# SCH_MulFuncPerCalendar_2024-10-28.net
KiCad netlist of a schematic drawn in EasyEDA
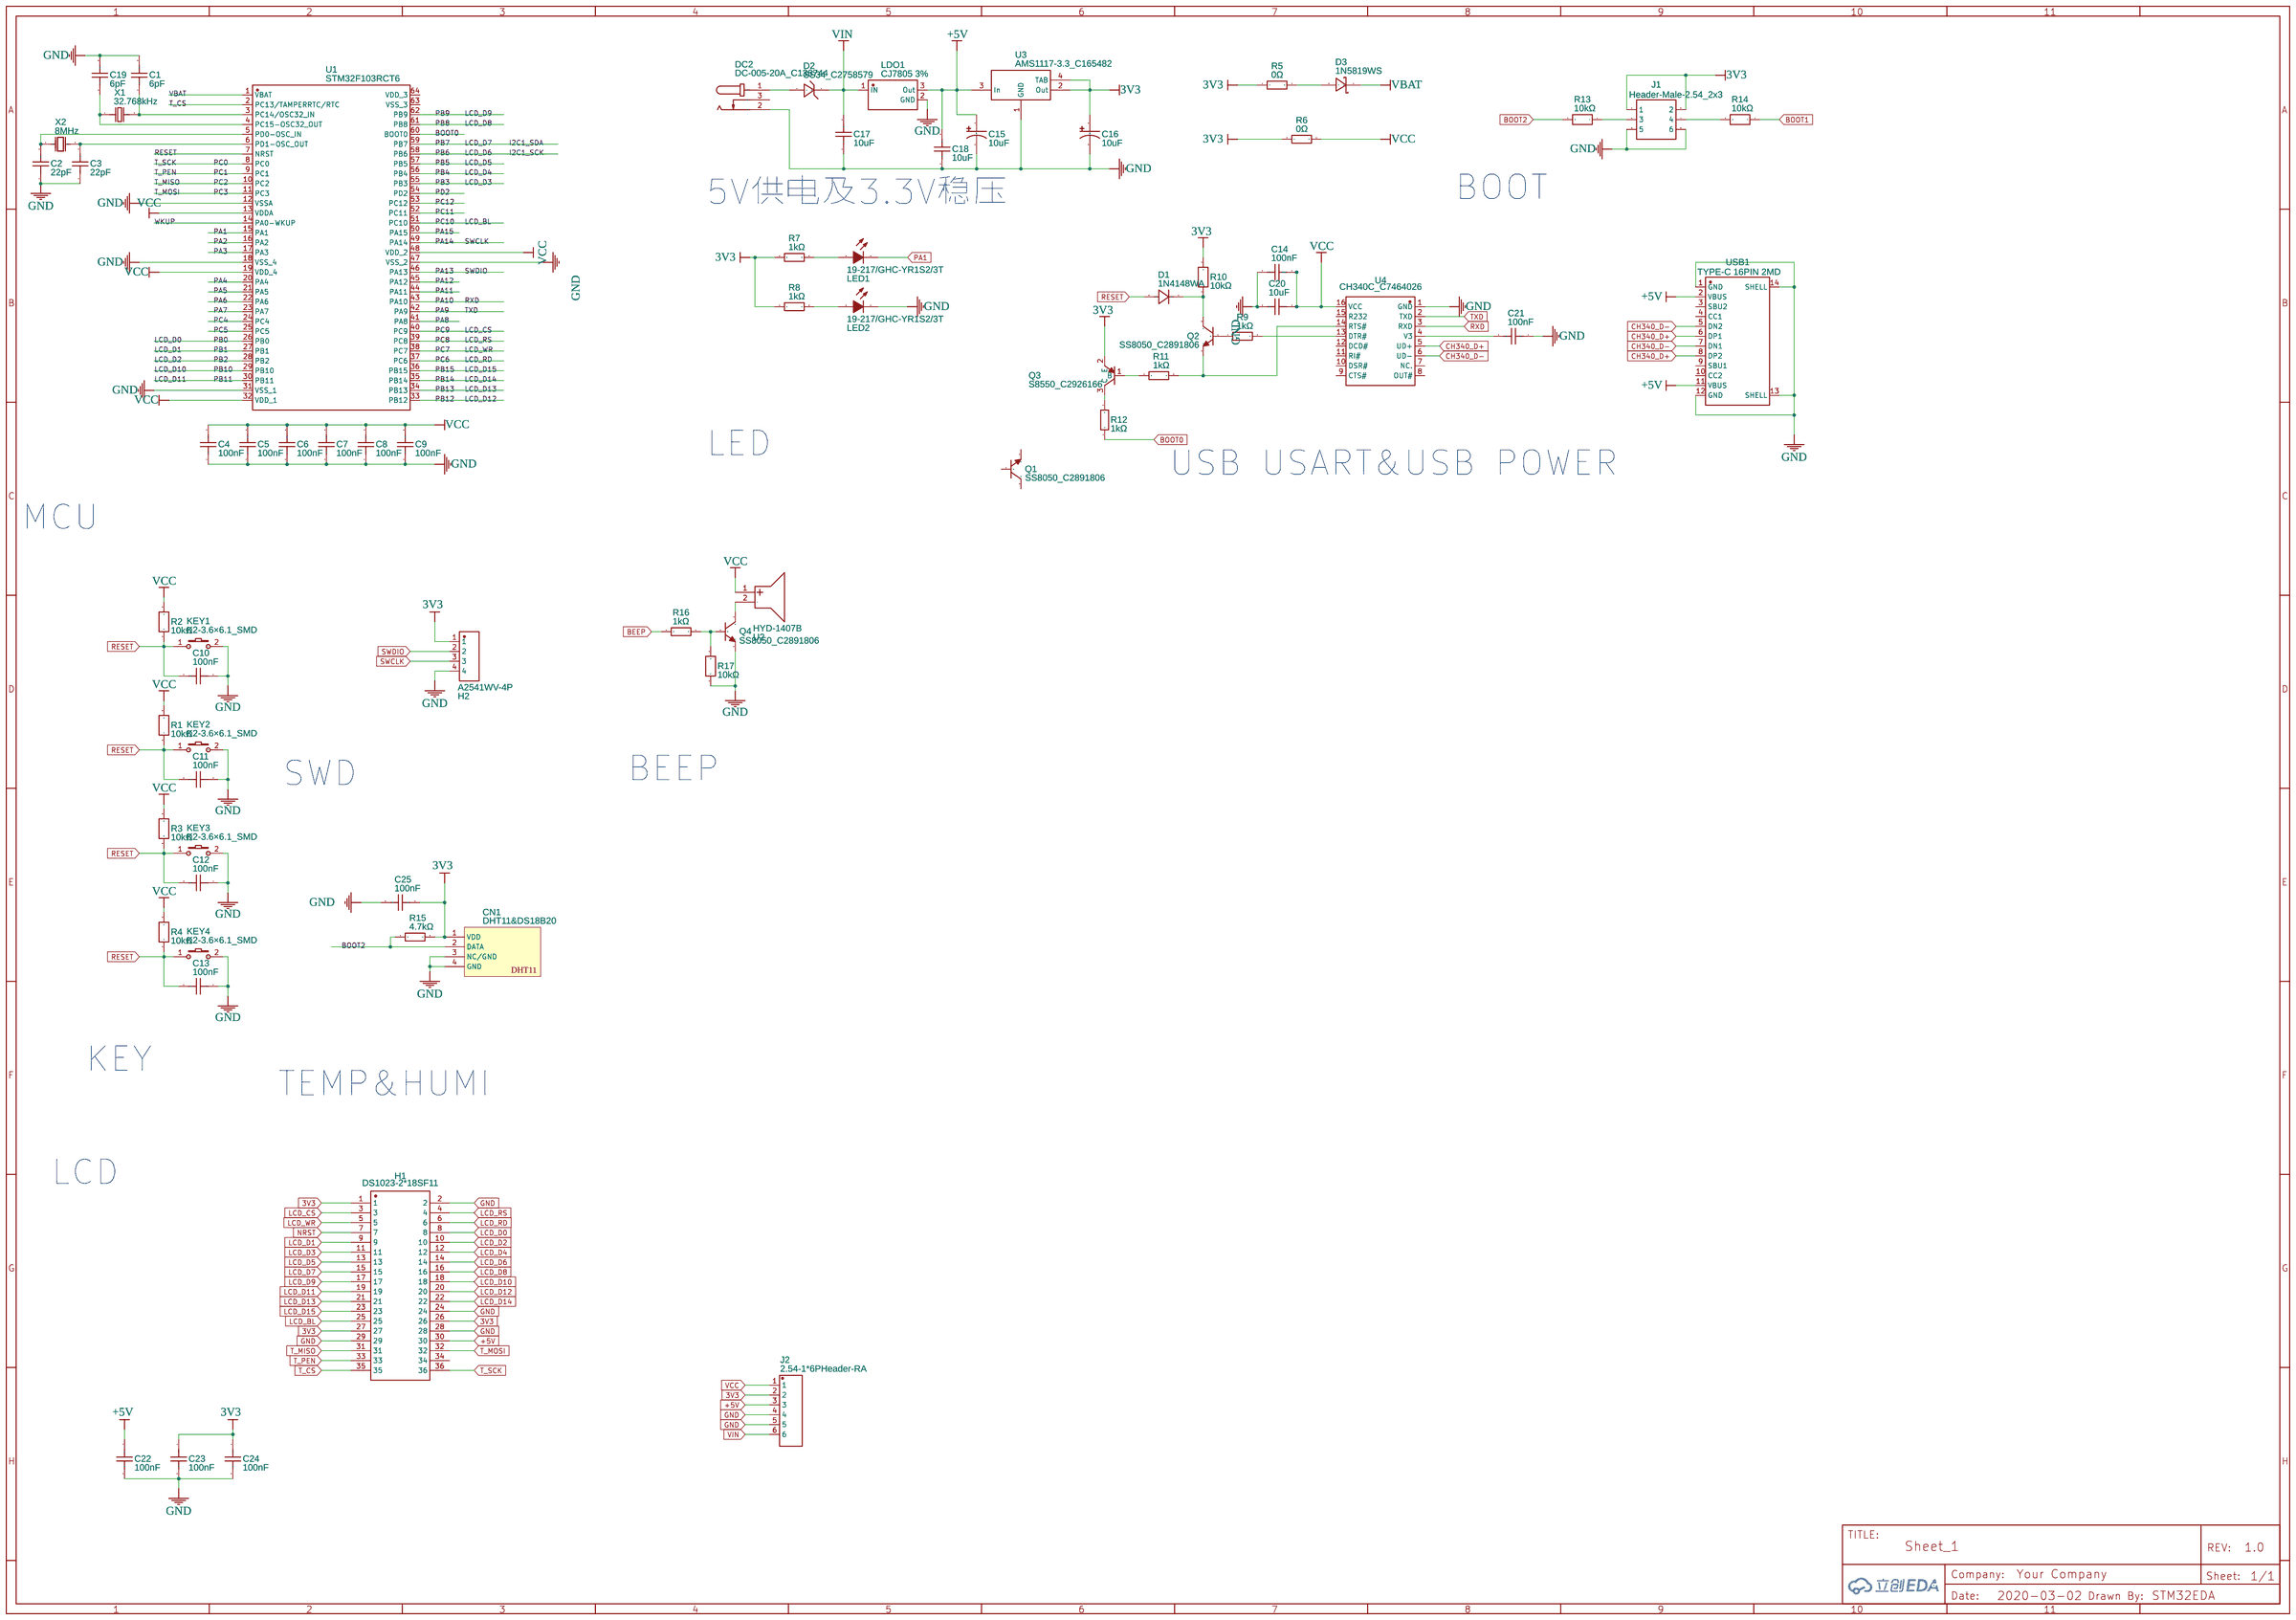
[diagram p0: schematic sheet]

(export (version "E")
  (design (tool "Eeschema 10.0.6"))
  (components
    (comp (ref "C1")
      (value "6pF")
      (fields (field (name "Manufacturer Part") "0603N6R0B500CT") (field (name "Manufacturer") "Walsin(华新科)"))
      (libsource (lib "") (part "0603N6R0B500CT"))
    )
    (comp (ref "C2")
      (value "22pF")
      (fields (field (name "Manufacturer Part") "06035A220FAT2A") (field (name "Manufacturer") "Kyocera AVX"))
      (libsource (lib "") (part "06035A220FAT2A"))
    )
    (comp (ref "C3")
      (value "22pF")
      (fields (field (name "Manufacturer Part") "06035A220FAT2A") (field (name "Manufacturer") "Kyocera AVX"))
      (libsource (lib "") (part "06035A220FAT2A"))
    )
    (comp (ref "C4")
      (value "100nF")
      (fields (field (name "Manufacturer Part") "C1608X7R1E104M080AA") (field (name "Manufacturer") "TDK"))
      (libsource (lib "") (part "C1608X7R1E104M080AA"))
    )
    (comp (ref "C5")
      (value "100nF")
      (fields (field (name "Manufacturer Part") "C1608X7R1E104M080AA") (field (name "Manufacturer") "TDK"))
      (libsource (lib "") (part "C1608X7R1E104M080AA"))
    )
    (comp (ref "C6")
      (value "100nF")
      (fields (field (name "Manufacturer Part") "C1608X7R1E104M080AA") (field (name "Manufacturer") "TDK"))
      (libsource (lib "") (part "C1608X7R1E104M080AA"))
    )
    (comp (ref "C7")
      (value "100nF")
      (fields (field (name "Manufacturer Part") "C1608X7R1E104M080AA") (field (name "Manufacturer") "TDK"))
      (libsource (lib "") (part "C1608X7R1E104M080AA"))
    )
    (comp (ref "C8")
      (value "100nF")
      (fields (field (name "Manufacturer Part") "C1608X7R1E104M080AA") (field (name "Manufacturer") "TDK"))
      (libsource (lib "") (part "C1608X7R1E104M080AA"))
    )
    (comp (ref "C9")
      (value "100nF")
      (fields (field (name "Manufacturer Part") "C1608X7R1E104M080AA") (field (name "Manufacturer") "TDK"))
      (libsource (lib "") (part "C1608X7R1E104M080AA"))
    )
    (comp (ref "C10")
      (value "100nF")
      (fields
        (field (name "Manufacturer Part") "CC0603JRX7R8BB104")
        (field (name "Manufacturer") "YAGEO(国巨)")
      )
      (libsource (lib "") (part "CC0603JRX7R8BB104"))
    )
    (comp (ref "C11")
      (value "100nF")
      (fields
        (field (name "Manufacturer Part") "CC0603JRX7R8BB104")
        (field (name "Manufacturer") "YAGEO(国巨)")
      )
      (libsource (lib "") (part "CC0603JRX7R8BB104"))
    )
    (comp (ref "C12")
      (value "100nF")
      (fields
        (field (name "Manufacturer Part") "CC0603JRX7R8BB104")
        (field (name "Manufacturer") "YAGEO(国巨)")
      )
      (libsource (lib "") (part "CC0603JRX7R8BB104"))
    )
    (comp (ref "C13")
      (value "100nF")
      (fields
        (field (name "Manufacturer Part") "CC0603JRX7R8BB104")
        (field (name "Manufacturer") "YAGEO(国巨)")
      )
      (libsource (lib "") (part "CC0603JRX7R8BB104"))
    )
    (comp (ref "C14")
      (value "100nF")
      (fields
        (field (name "Manufacturer Part") "CC0603JRX7R8BB104")
        (field (name "Manufacturer") "YAGEO(国巨)")
      )
      (libsource (lib "") (part "CC0603JRX7R8BB104"))
    )
    (comp (ref "C15")
      (value "10uF")
      (fields
        (field (name "Manufacturer Part") "CA45-A-10V-10μF-K")
        (field (name "Manufacturer") "TORCH(火炬)")
      )
      (libsource (lib "") (part "CA45-A-10V-10μF-K_1"))
    )
    (comp (ref "C16")
      (value "10uF")
      (fields
        (field (name "Manufacturer Part") "CA45-A-10V-10μF-K")
        (field (name "Manufacturer") "TORCH(火炬)")
      )
      (libsource (lib "") (part "CA45-A-10V-10μF-K"))
    )
    (comp (ref "C17")
      (value "10uF")
      (fields
        (field (name "Manufacturer Part") "GRM188R6YA106MA73D")
        (field (name "Manufacturer") "muRata(村田)")
      )
      (libsource (lib "") (part "GRM188R6YA106MA73D"))
    )
    (comp (ref "C18")
      (value "10uF")
      (fields
        (field (name "Manufacturer Part") "GRM188R6YA106MA73D")
        (field (name "Manufacturer") "muRata(村田)")
      )
      (libsource (lib "") (part "GRM188R6YA106MA73D"))
    )
    (comp (ref "C19")
      (value "6pF")
      (fields (field (name "Manufacturer Part") "0603N6R0B500CT") (field (name "Manufacturer") "Walsin(华新科)"))
      (libsource (lib "") (part "0603N6R0B500CT"))
    )
    (comp (ref "C20")
      (value "10uF")
      (fields
        (field (name "Manufacturer Part") "GRM188R6YA106MA73D")
        (field (name "Manufacturer") "muRata(村田)")
      )
      (libsource (lib "") (part "GRM188R6YA106MA73D_1"))
    )
    (comp (ref "C21")
      (value "100nF")
      (fields
        (field (name "Manufacturer Part") "CC0603JRX7R8BB104")
        (field (name "Manufacturer") "YAGEO(国巨)")
      )
      (libsource (lib "") (part "CC0603JRX7R8BB104"))
    )
    (comp (ref "C22")
      (value "100nF")
      (fields
        (field (name "Manufacturer Part") "CC0603JRX7R8BB104")
        (field (name "Manufacturer") "YAGEO(国巨)")
      )
      (libsource (lib "") (part "CC0603JRX7R8BB104_1"))
    )
    (comp (ref "C23")
      (value "100nF")
      (fields
        (field (name "Manufacturer Part") "CC0603JRX7R8BB104")
        (field (name "Manufacturer") "YAGEO(国巨)")
      )
      (libsource (lib "") (part "CC0603JRX7R8BB104_1"))
    )
    (comp (ref "C24")
      (value "100nF")
      (fields
        (field (name "Manufacturer Part") "CC0603JRX7R8BB104")
        (field (name "Manufacturer") "YAGEO(国巨)")
      )
      (libsource (lib "") (part "CC0603JRX7R8BB104_1"))
    )
    (comp (ref "C25")
      (value "100nF")
      (fields
        (field (name "Manufacturer Part") "CC0603JRX7R8BB104")
        (field (name "Manufacturer") "YAGEO(国巨)")
      )
      (libsource (lib "") (part "CC0603JRX7R8BB104"))
    )
    (comp (ref "CN1") (value "DHT11&DS18B20") (libsource (lib "") (part "DHT11&DS18B20")))
    (comp (ref "D1")
      (value "1N4148WA")
      (fields (field (name "Manufacturer") "PJSEMI(平晶微)"))
      (libsource (lib "") (part "1N4148WA"))
    )
    (comp (ref "D2")
      (value "SS34_C2758579")
      (fields (field (name "Manufacturer Part") "SS34") (field (name "Manufacturer") "UMW(友台半导体)"))
      (libsource (lib "") (part "SS34_C2758579"))
    )
    (comp (ref "D3")
      (value "1N5819WS")
      (fields (field (name "Manufacturer") "Hottech(合科泰)"))
      (libsource (lib "") (part "1N5819WS"))
    )
    (comp (ref "DC2")
      (value "DC-005-20A_C136744")
      (fields (field (name "Manufacturer Part") "DC-005-20A") (field (name "Manufacturer") "韩国韩荣"))
      (libsource (lib "") (part "DC-005-20A_C136744"))
    )
    (comp (ref "H1")
      (value "DS1023-2*18SF11")
      (fields (field (name "Manufacturer") "CONNFLY"))
      (libsource (lib "") (part "DS1023-2*18SF11"))
    )
    (comp (ref "H2")
      (value "A2541WV-4P")
      (fields (field (name "Manufacturer") "CJT(长江连接器)"))
      (libsource (lib "") (part "A2541WV-4P"))
    )
    (comp (ref "J1")
      (value "Header-Male-2.54_2x3")
      (fields (field (name "Manufacturer Part") "2.54-2*3P针") (field (name "Manufacturer") "BOOMELE(博穆精密)"))
      (libsource (lib "") (part "Header-Male-2.54_2x3"))
    )
    (comp (ref "J2")
      (value "2.54-1*6PHeader-RA")
      (fields
        (field (name "Manufacturer Part") "2.54-1*6P反弯排针")
        (field (name "Manufacturer") "BOOMELE(博穆精密)")
      )
      (libsource (lib "") (part "2.54-1*6PHeader-RA"))
    )
    (comp (ref "KEY1")
      (value "K2-3.6×6.1_SMD")
      (fields (field (name "Manufacturer Part") "K2-1107ST-A4SW-06"))
      (libsource (lib "") (part "K2-3.6×6.1_SMD"))
    )
    (comp (ref "KEY2")
      (value "K2-3.6×6.1_SMD")
      (fields (field (name "Manufacturer Part") "K2-1107ST-A4SW-06"))
      (libsource (lib "") (part "K2-3.6×6.1_SMD"))
    )
    (comp (ref "KEY3")
      (value "K2-3.6×6.1_SMD")
      (fields (field (name "Manufacturer Part") "K2-1107ST-A4SW-06"))
      (libsource (lib "") (part "K2-3.6×6.1_SMD"))
    )
    (comp (ref "KEY4")
      (value "K2-3.6×6.1_SMD")
      (fields (field (name "Manufacturer Part") "K2-1107ST-A4SW-06"))
      (libsource (lib "") (part "K2-3.6×6.1_SMD"))
    )
    (comp (ref "LDO1")
      (value "CJ7805 3%")
      (fields (field (name "Manufacturer") "CJ(江苏长电/长晶)"))
      (libsource (lib "") (part "CJ7805 3%"))
    )
    (comp (ref "LED1")
      (value "19-217/GHC-YR1S2/3T")
      (fields (field (name "Manufacturer") "EVERLIGHT(亿光)"))
      (libsource (lib "") (part "19-217/GHC-YR1S2/3T"))
    )
    (comp (ref "LED2")
      (value "19-217/GHC-YR1S2/3T")
      (fields (field (name "Manufacturer") "EVERLIGHT(亿光)"))
      (libsource (lib "") (part "19-217/GHC-YR1S2/3T"))
    )
    (comp (ref "Q1")
      (value "SS8050_C2891806")
      (fields (field (name "Manufacturer Part") "SS8050") (field (name "Manufacturer") "YONGYUTAI(永裕泰)"))
      (libsource (lib "") (part "SS8050_C2891806_2"))
    )
    (comp (ref "Q2")
      (value "SS8050_C2891806")
      (fields (field (name "Manufacturer Part") "SS8050") (field (name "Manufacturer") "YONGYUTAI(永裕泰)"))
      (libsource (lib "") (part "SS8050_C2891806"))
    )
    (comp (ref "Q3")
      (value "S8550_C2926166")
      (fields (field (name "Manufacturer Part") "S8550") (field (name "Manufacturer") "FOSAN(富信)"))
      (libsource (lib "") (part "S8550_C2926166"))
    )
    (comp (ref "Q4")
      (value "SS8050_C2891806")
      (fields (field (name "Manufacturer Part") "SS8050") (field (name "Manufacturer") "YONGYUTAI(永裕泰)"))
      (libsource (lib "") (part "SS8050_C2891806_1"))
    )
    (comp (ref "R1")
      (value "10kΩ")
      (fields
        (field (name "Manufacturer Part") "SC0603J1002F2BNRH")
        (field (name "Manufacturer") "Sunway(信维通信)")
      )
      (libsource (lib "") (part "SC0603J1002F2BNRH"))
    )
    (comp (ref "R2")
      (value "10kΩ")
      (fields
        (field (name "Manufacturer Part") "SC0603J1002F2BNRH")
        (field (name "Manufacturer") "Sunway(信维通信)")
      )
      (libsource (lib "") (part "SC0603J1002F2BNRH"))
    )
    (comp (ref "R3")
      (value "10kΩ")
      (fields
        (field (name "Manufacturer Part") "SC0603J1002F2BNRH")
        (field (name "Manufacturer") "Sunway(信维通信)")
      )
      (libsource (lib "") (part "SC0603J1002F2BNRH"))
    )
    (comp (ref "R4")
      (value "10kΩ")
      (fields
        (field (name "Manufacturer Part") "SC0603J1002F2BNRH")
        (field (name "Manufacturer") "Sunway(信维通信)")
      )
      (libsource (lib "") (part "SC0603J1002F2BNRH"))
    )
    (comp (ref "R5")
      (value "0Ω")
      (fields
        (field (name "Manufacturer Part") "0603WAF0000T5E")
        (field (name "Manufacturer") "UNI-ROYAL(厚声)")
      )
      (libsource (lib "") (part "0603WAF0000T5E"))
    )
    (comp (ref "R6")
      (value "0Ω")
      (fields
        (field (name "Manufacturer Part") "0603WAF0000T5E")
        (field (name "Manufacturer") "UNI-ROYAL(厚声)")
      )
      (libsource (lib "") (part "0603WAF0000T5E"))
    )
    (comp (ref "R7")
      (value "1kΩ")
      (fields
        (field (name "Manufacturer Part") "0603WAF1001T5E")
        (field (name "Manufacturer") "UNI-ROYAL(厚声)")
      )
      (libsource (lib "") (part "0603WAF1001T5E"))
    )
    (comp (ref "R8")
      (value "1kΩ")
      (fields
        (field (name "Manufacturer Part") "0603WAF1001T5E")
        (field (name "Manufacturer") "UNI-ROYAL(厚声)")
      )
      (libsource (lib "") (part "0603WAF1001T5E"))
    )
    (comp (ref "R9")
      (value "1kΩ")
      (fields
        (field (name "Manufacturer Part") "0603WAF1001T5E")
        (field (name "Manufacturer") "UNI-ROYAL(厚声)")
      )
      (libsource (lib "") (part "0603WAF1001T5E"))
    )
    (comp (ref "R10")
      (value "10kΩ")
      (fields
        (field (name "Manufacturer Part") "SC0603J1002F2BNRH")
        (field (name "Manufacturer") "Sunway(信维通信)")
      )
      (libsource (lib "") (part "SC0603J1002F2BNRH"))
    )
    (comp (ref "R11")
      (value "1kΩ")
      (fields
        (field (name "Manufacturer Part") "0603WAF1001T5E")
        (field (name "Manufacturer") "UNI-ROYAL(厚声)")
      )
      (libsource (lib "") (part "0603WAF1001T5E"))
    )
    (comp (ref "R12")
      (value "1kΩ")
      (fields
        (field (name "Manufacturer Part") "0603WAF1001T5E")
        (field (name "Manufacturer") "UNI-ROYAL(厚声)")
      )
      (libsource (lib "") (part "0603WAF1001T5E_2"))
    )
    (comp (ref "R13")
      (value "10kΩ")
      (fields
        (field (name "Manufacturer Part") "SC0603J1002F2BNRH")
        (field (name "Manufacturer") "Sunway(信维通信)")
      )
      (libsource (lib "") (part "SC0603J1002F2BNRH_1"))
    )
    (comp (ref "R14")
      (value "10kΩ")
      (fields
        (field (name "Manufacturer Part") "SC0603J1002F2BNRH")
        (field (name "Manufacturer") "Sunway(信维通信)")
      )
      (libsource (lib "") (part "SC0603J1002F2BNRH_1"))
    )
    (comp (ref "R15")
      (value "4.7kΩ")
      (fields (field (name "Manufacturer Part") "ACD03K4701FT") (field (name "Manufacturer") "FH(风华)"))
      (libsource (lib "") (part "4.7K  0603  SOP"))
    )
    (comp (ref "R16")
      (value "1kΩ")
      (fields
        (field (name "Manufacturer Part") "0603WAF1001T5E")
        (field (name "Manufacturer") "UNI-ROYAL(厚声)")
      )
      (libsource (lib "") (part "0603WAF1001T5E_1"))
    )
    (comp (ref "R17")
      (value "10kΩ")
      (fields
        (field (name "Manufacturer Part") "SC0603J1002F2BNRH")
        (field (name "Manufacturer") "Sunway(信维通信)")
      )
      (libsource (lib "") (part "SC0603J1002F2BNRH"))
    )
    (comp (ref "U1")
      (value "STM32F103RCT6")
      (fields (field (name "Manufacturer") "ST(意法半导体)"))
      (libsource (lib "") (part "STM32F103RCT6"))
    )
    (comp (ref "U2")
      (value "HYD-1407B")
      (fields (field (name "Manufacturer") "HYDZ(华宇)"))
      (libsource (lib "") (part "HYD-1407B"))
    )
    (comp (ref "U3")
      (value "AMS1117-3.3_C165482")
      (fields (field (name "Manufacturer Part") "SK1117-3.3") (field (name "Manufacturer") "SHIKUES(时科)"))
      (libsource (lib "") (part "AMS1117-3.3_C165482"))
    )
    (comp (ref "U4")
      (value "CH340C_C7464026")
      (fields (field (name "Manufacturer Part") "CH340C") (field (name "Manufacturer") "WCH(南京沁恒)"))
      (libsource (lib "") (part "CH340C_C7464026"))
    )
    (comp (ref "USB1")
      (value "TYPE-C 16PIN 2MD")
      (fields
        (field (name "Manufacturer Part") "TYPE-C 16PIN 2MD(073)")
        (field (name "Manufacturer") "SHOU HAN(首韩)")
      )
      (libsource (lib "") (part "TYPE-C 16PIN 2MD(073)"))
    )
    (comp (ref "X1")
      (value "32.768kHz")
      (fields (field (name "Manufacturer Part") "Q13FC13500002") (field (name "Manufacturer") "EPSON(爱普生)"))
      (libsource (lib "") (part "Q13FC1350000200"))
    )
    (comp (ref "X2")
      (value "8MHz")
      (fields
        (field (name "Manufacturer Part") "ESB8.00000F20E22")
        (field (name "Manufacturer") "HOSONIC(鸿星)")
      )
      (libsource (lib "") (part "ESB8.00000F20E22"))
    )
  )
  (nets
    (net (code "1") (name "+5V") (class "Default")
      (node (ref "C15") (pin "1") (pinfunction "1_1") (pintype "unspecified"))
      (node (ref "C18") (pin "2") (pinfunction "2_2") (pintype "unspecified"))
      (node (ref "C22") (pin "1") (pinfunction "1_1") (pintype "unspecified"))
      (node (ref "H1") (pin "30") (pinfunction "30_30") (pintype "unspecified"))
      (node (ref "J2") (pin "3") (pinfunction "3_3") (pintype "unspecified"))
      (node (ref "LDO1") (pin "3") (pinfunction "Out_3") (pintype "unspecified"))
      (node (ref "U3") (pin "3") (pinfunction "In_3") (pintype "unspecified"))
      (node (ref "USB1") (pin "11") (pinfunction "VBUS_11") (pintype "unspecified"))
      (node (ref "USB1") (pin "2") (pinfunction "VBUS_2") (pintype "unspecified"))
    )
    (net (code "2") (name "/PA2") (class "Default")
      (node (ref "U1") (pin "16") (pinfunction "PA2_16") (pintype "unspecified"))
    )
    (net (code "3") (name "/PA3") (class "Default")
      (node (ref "U1") (pin "17") (pinfunction "PA3_17") (pintype "unspecified"))
    )
    (net (code "4") (name "/PA4") (class "Default")
      (node (ref "U1") (pin "20") (pinfunction "PA4_20") (pintype "unspecified"))
    )
    (net (code "5") (name "/PA5") (class "Default")
      (node (ref "U1") (pin "21") (pinfunction "PA5_21") (pintype "unspecified"))
    )
    (net (code "6") (name "/PA6") (class "Default")
      (node (ref "U1") (pin "22") (pinfunction "PA6_22") (pintype "unspecified"))
    )
    (net (code "7") (name "/PA7") (class "Default")
      (node (ref "U1") (pin "23") (pinfunction "PA7_23") (pintype "unspecified"))
    )
    (net (code "8") (name "/PA8") (class "Default")
      (node (ref "U1") (pin "41") (pinfunction "PA8_41") (pintype "unspecified"))
    )
    (net (code "9") (name "/PA11") (class "Default")
      (node (ref "U1") (pin "44") (pinfunction "PA11_44") (pintype "unspecified"))
    )
    (net (code "10") (name "/PA12") (class "Default")
      (node (ref "U1") (pin "45") (pinfunction "PA12_45") (pintype "unspecified"))
    )
    (net (code "11") (name "/PA15") (class "Default")
      (node (ref "U1") (pin "50") (pinfunction "PA15_50") (pintype "unspecified"))
    )
    (net (code "12") (name "/PC4") (class "Default")
      (node (ref "U1") (pin "24") (pinfunction "PC4_24") (pintype "unspecified"))
    )
    (net (code "13") (name "/PC5") (class "Default")
      (node (ref "U1") (pin "25") (pinfunction "PC5_25") (pintype "unspecified"))
    )
    (net (code "14") (name "/PC11") (class "Default")
      (node (ref "U1") (pin "52") (pinfunction "PC11_52") (pintype "unspecified"))
    )
    (net (code "15") (name "/PC12") (class "Default")
      (node (ref "U1") (pin "53") (pinfunction "PC12_53") (pintype "unspecified"))
    )
    (net (code "16") (name "/PD2") (class "Default")
      (node (ref "U1") (pin "54") (pinfunction "PD2_54") (pintype "unspecified"))
    )
    (net (code "17") (name "/WKUP") (class "Default")
      (node (ref "U1") (pin "14") (pinfunction "PA0-WKUP_14") (pintype "unspecified"))
    )
    (net (code "18") (name "3V3") (class "Default")
      (node (ref "C16") (pin "1") (pinfunction "1_1") (pintype "unspecified"))
      (node (ref "C23") (pin "1") (pinfunction "1_1") (pintype "unspecified"))
      (node (ref "C24") (pin "1") (pinfunction "1_1") (pintype "unspecified"))
      (node (ref "C25") (pin "1") (pinfunction "1_1") (pintype "unspecified"))
      (node (ref "CN1") (pin "1") (pinfunction "VDD_1") (pintype "unspecified"))
      (node (ref "H1") (pin "1") (pinfunction "1_1") (pintype "unspecified"))
      (node (ref "H1") (pin "26") (pinfunction "26_26") (pintype "unspecified"))
      (node (ref "H1") (pin "27") (pinfunction "27_27") (pintype "unspecified"))
      (node (ref "H2") (pin "1") (pinfunction "1_1") (pintype "unspecified"))
      (node (ref "J1") (pin "1") (pinfunction "1_1") (pintype "input"))
      (node (ref "J1") (pin "2") (pinfunction "2_2") (pintype "input"))
      (node (ref "J2") (pin "2") (pinfunction "2_2") (pintype "unspecified"))
      (node (ref "Q3") (pin "2") (pinfunction "E_2") (pintype "input"))
      (node (ref "R10") (pin "2") (pinfunction "2_2") (pintype "unspecified"))
      (node (ref "R15") (pin "2") (pinfunction "2_2") (pintype "unspecified"))
      (node (ref "R5") (pin "1") (pinfunction "1_1") (pintype "input"))
      (node (ref "R6") (pin "1") (pinfunction "1_1") (pintype "input"))
      (node (ref "R7") (pin "1") (pinfunction "1_1") (pintype "input"))
      (node (ref "R8") (pin "1") (pinfunction "1_1") (pintype "input"))
      (node (ref "U3") (pin "2") (pinfunction "Out_2") (pintype "unspecified"))
      (node (ref "U3") (pin "4") (pinfunction "TAB_4") (pintype "unspecified"))
    )
    (net (code "19") (name "BEEP") (class "Default")
      (node (ref "R16") (pin "2") (pinfunction "2_2") (pintype "input"))
    )
    (net (code "20") (name "BOOT0") (class "Default")
      (node (ref "R12") (pin "1") (pinfunction "1_1") (pintype "input"))
      (node (ref "U1") (pin "60") (pinfunction "BOOT0_60") (pintype "unspecified"))
    )
    (net (code "21") (name "BOOT1") (class "Default")
      (node (ref "R14") (pin "1") (pinfunction "1_1") (pintype "unspecified"))
    )
    (net (code "22") (name "BOOT2") (class "Default")
      (node (ref "CN1") (pin "2") (pinfunction "DATA_2") (pintype "unspecified"))
      (node (ref "R13") (pin "2") (pinfunction "2_2") (pintype "unspecified"))
      (node (ref "R15") (pin "1") (pinfunction "1_1") (pintype "unspecified"))
    )
    (net (code "23") (name "CH340_D+") (class "Default")
      (node (ref "U4") (pin "5") (pinfunction "UD+_5") (pintype "unspecified"))
      (node (ref "USB1") (pin "6") (pinfunction "DP1_6") (pintype "unspecified"))
      (node (ref "USB1") (pin "8") (pinfunction "DP2_8") (pintype "unspecified"))
    )
    (net (code "24") (name "CH340_D-") (class "Default")
      (node (ref "U4") (pin "6") (pinfunction "UD-_6") (pintype "unspecified"))
      (node (ref "USB1") (pin "5") (pinfunction "DN2_5") (pintype "unspecified"))
      (node (ref "USB1") (pin "7") (pinfunction "DN1_7") (pintype "unspecified"))
    )
    (net (code "25") (name "GND") (class "Default")
      (node (ref "C1") (pin "2") (pinfunction "2_2") (pintype "unspecified"))
      (node (ref "C10") (pin "1") (pinfunction "1_1") (pintype "unspecified"))
      (node (ref "C11") (pin "1") (pinfunction "1_1") (pintype "unspecified"))
      (node (ref "C12") (pin "1") (pinfunction "1_1") (pintype "unspecified"))
      (node (ref "C13") (pin "1") (pinfunction "1_1") (pintype "unspecified"))
      (node (ref "C14") (pin "2") (pinfunction "2_2") (pintype "unspecified"))
      (node (ref "C15") (pin "2") (pinfunction "2_2") (pintype "unspecified"))
      (node (ref "C16") (pin "2") (pinfunction "2_2") (pintype "unspecified"))
      (node (ref "C17") (pin "1") (pinfunction "1_1") (pintype "unspecified"))
      (node (ref "C18") (pin "1") (pinfunction "1_1") (pintype "unspecified"))
      (node (ref "C19") (pin "2") (pinfunction "2_2") (pintype "unspecified"))
      (node (ref "C2") (pin "1") (pinfunction "1_1") (pintype "unspecified"))
      (node (ref "C20") (pin "2") (pinfunction "2_2") (pintype "unspecified"))
      (node (ref "C21") (pin "1") (pinfunction "1_1") (pintype "unspecified"))
      (node (ref "C22") (pin "2") (pinfunction "2_2") (pintype "unspecified"))
      (node (ref "C23") (pin "2") (pinfunction "2_2") (pintype "unspecified"))
      (node (ref "C24") (pin "2") (pinfunction "2_2") (pintype "unspecified"))
      (node (ref "C25") (pin "2") (pinfunction "2_2") (pintype "unspecified"))
      (node (ref "C3") (pin "1") (pinfunction "1_1") (pintype "unspecified"))
      (node (ref "C4") (pin "1") (pinfunction "1_1") (pintype "unspecified"))
      (node (ref "C5") (pin "1") (pinfunction "1_1") (pintype "unspecified"))
      (node (ref "C6") (pin "1") (pinfunction "1_1") (pintype "unspecified"))
      (node (ref "C7") (pin "1") (pinfunction "1_1") (pintype "unspecified"))
      (node (ref "C8") (pin "1") (pinfunction "1_1") (pintype "unspecified"))
      (node (ref "C9") (pin "1") (pinfunction "1_1") (pintype "unspecified"))
      (node (ref "CN1") (pin "3") (pinfunction "NC/GND_3") (pintype "unspecified"))
      (node (ref "CN1") (pin "4") (pinfunction "GND_4") (pintype "unspecified"))
      (node (ref "DC2") (pin "2") (pinfunction "2_2") (pintype "unspecified"))
      (node (ref "H1") (pin "2") (pinfunction "2_2") (pintype "unspecified"))
      (node (ref "H1") (pin "24") (pinfunction "24_24") (pintype "unspecified"))
      (node (ref "H1") (pin "28") (pinfunction "28_28") (pintype "unspecified"))
      (node (ref "H1") (pin "29") (pinfunction "29_29") (pintype "unspecified"))
      (node (ref "H2") (pin "4") (pinfunction "4_4") (pintype "unspecified"))
      (node (ref "J1") (pin "5") (pinfunction "5_5") (pintype "input"))
      (node (ref "J1") (pin "6") (pinfunction "6_6") (pintype "input"))
      (node (ref "J2") (pin "4") (pinfunction "4_4") (pintype "unspecified"))
      (node (ref "J2") (pin "5") (pinfunction "5_5") (pintype "unspecified"))
      (node (ref "KEY1") (pin "2") (pinfunction "2_2") (pintype "unspecified"))
      (node (ref "KEY2") (pin "2") (pinfunction "2_2") (pintype "unspecified"))
      (node (ref "KEY3") (pin "2") (pinfunction "2_2") (pintype "unspecified"))
      (node (ref "KEY4") (pin "2") (pinfunction "2_2") (pintype "unspecified"))
      (node (ref "LDO1") (pin "2") (pinfunction "GND_2") (pintype "unspecified"))
      (node (ref "LED2") (pin "1") (pinfunction "C_1") (pintype "input"))
      (node (ref "Q4") (pin "2") (pinfunction "E_2") (pintype "input"))
      (node (ref "R17") (pin "1") (pinfunction "1_1") (pintype "unspecified"))
      (node (ref "U1") (pin "12") (pinfunction "VSSA_12") (pintype "unspecified"))
      (node (ref "U1") (pin "18") (pinfunction "VSS_4_18") (pintype "unspecified"))
      (node (ref "U1") (pin "31") (pinfunction "VSS_1_31") (pintype "unspecified"))
      (node (ref "U1") (pin "47") (pinfunction "VSS_2_47") (pintype "unspecified"))
      (node (ref "U3") (pin "1") (pinfunction "GND_1") (pintype "unspecified"))
      (node (ref "U4") (pin "1") (pinfunction "GND_1") (pintype "unspecified"))
      (node (ref "USB1") (pin "1") (pinfunction "GND_1") (pintype "unspecified"))
      (node (ref "USB1") (pin "12") (pinfunction "GND_12") (pintype "unspecified"))
      (node (ref "USB1") (pin "13") (pinfunction "SHELL_13") (pintype "unspecified"))
      (node (ref "USB1") (pin "14") (pinfunction "SHELL_14") (pintype "unspecified"))
    )
    (net (code "26") (name "LCD_BL") (class "Default")
      (node (ref "H1") (pin "25") (pinfunction "25_25") (pintype "unspecified"))
      (node (ref "U1") (pin "51") (pinfunction "PC10_51") (pintype "unspecified"))
    )
    (net (code "27") (name "LCD_CS") (class "Default")
      (node (ref "H1") (pin "3") (pinfunction "3_3") (pintype "unspecified"))
      (node (ref "U1") (pin "40") (pinfunction "PC9_40") (pintype "unspecified"))
    )
    (net (code "28") (name "LCD_D0") (class "Default")
      (node (ref "H1") (pin "8") (pinfunction "8_8") (pintype "unspecified"))
      (node (ref "U1") (pin "26") (pinfunction "PB0_26") (pintype "unspecified"))
    )
    (net (code "29") (name "LCD_D1") (class "Default")
      (node (ref "H1") (pin "9") (pinfunction "9_9") (pintype "unspecified"))
      (node (ref "U1") (pin "27") (pinfunction "PB1_27") (pintype "unspecified"))
    )
    (net (code "30") (name "LCD_D2") (class "Default")
      (node (ref "H1") (pin "10") (pinfunction "10_10") (pintype "unspecified"))
      (node (ref "U1") (pin "28") (pinfunction "PB2_28") (pintype "unspecified"))
    )
    (net (code "31") (name "LCD_D3") (class "Default")
      (node (ref "H1") (pin "11") (pinfunction "11_11") (pintype "unspecified"))
      (node (ref "U1") (pin "55") (pinfunction "PB3_55") (pintype "unspecified"))
    )
    (net (code "32") (name "LCD_D4") (class "Default")
      (node (ref "H1") (pin "12") (pinfunction "12_12") (pintype "unspecified"))
      (node (ref "U1") (pin "56") (pinfunction "PB4_56") (pintype "unspecified"))
    )
    (net (code "33") (name "LCD_D5") (class "Default")
      (node (ref "H1") (pin "13") (pinfunction "13_13") (pintype "unspecified"))
      (node (ref "U1") (pin "57") (pinfunction "PB5_57") (pintype "unspecified"))
    )
    (net (code "34") (name "LCD_D6") (class "Default")
      (node (ref "H1") (pin "14") (pinfunction "14_14") (pintype "unspecified"))
      (node (ref "U1") (pin "58") (pinfunction "PB6_58") (pintype "unspecified"))
    )
    (net (code "35") (name "LCD_D7") (class "Default")
      (node (ref "H1") (pin "15") (pinfunction "15_15") (pintype "unspecified"))
      (node (ref "U1") (pin "59") (pinfunction "PB7_59") (pintype "unspecified"))
    )
    (net (code "36") (name "LCD_D8") (class "Default")
      (node (ref "H1") (pin "16") (pinfunction "16_16") (pintype "unspecified"))
      (node (ref "U1") (pin "61") (pinfunction "PB8_61") (pintype "unspecified"))
    )
    (net (code "37") (name "LCD_D9") (class "Default")
      (node (ref "H1") (pin "17") (pinfunction "17_17") (pintype "unspecified"))
      (node (ref "U1") (pin "62") (pinfunction "PB9_62") (pintype "unspecified"))
    )
    (net (code "38") (name "LCD_D10") (class "Default")
      (node (ref "H1") (pin "18") (pinfunction "18_18") (pintype "unspecified"))
      (node (ref "U1") (pin "29") (pinfunction "PB10_29") (pintype "unspecified"))
    )
    (net (code "39") (name "LCD_D11") (class "Default")
      (node (ref "H1") (pin "19") (pinfunction "19_19") (pintype "unspecified"))
      (node (ref "U1") (pin "30") (pinfunction "PB11_30") (pintype "unspecified"))
    )
    (net (code "40") (name "LCD_D12") (class "Default")
      (node (ref "H1") (pin "20") (pinfunction "20_20") (pintype "unspecified"))
      (node (ref "U1") (pin "33") (pinfunction "PB12_33") (pintype "unspecified"))
    )
    (net (code "41") (name "LCD_D13") (class "Default")
      (node (ref "H1") (pin "21") (pinfunction "21_21") (pintype "unspecified"))
      (node (ref "U1") (pin "34") (pinfunction "PB13_34") (pintype "unspecified"))
    )
    (net (code "42") (name "LCD_D14") (class "Default")
      (node (ref "H1") (pin "22") (pinfunction "22_22") (pintype "unspecified"))
      (node (ref "U1") (pin "35") (pinfunction "PB14_35") (pintype "unspecified"))
    )
    (net (code "43") (name "LCD_D15") (class "Default")
      (node (ref "H1") (pin "23") (pinfunction "23_23") (pintype "unspecified"))
      (node (ref "U1") (pin "36") (pinfunction "PB15_36") (pintype "unspecified"))
    )
    (net (code "44") (name "LCD_RD") (class "Default")
      (node (ref "H1") (pin "6") (pinfunction "6_6") (pintype "unspecified"))
      (node (ref "U1") (pin "37") (pinfunction "PC6_37") (pintype "unspecified"))
    )
    (net (code "45") (name "LCD_RS") (class "Default")
      (node (ref "H1") (pin "4") (pinfunction "4_4") (pintype "unspecified"))
      (node (ref "U1") (pin "39") (pinfunction "PC8_39") (pintype "unspecified"))
    )
    (net (code "46") (name "LCD_WR") (class "Default")
      (node (ref "H1") (pin "5") (pinfunction "5_5") (pintype "unspecified"))
      (node (ref "U1") (pin "38") (pinfunction "PC7_38") (pintype "unspecified"))
    )
    (net (code "47") (name "NRST") (class "Default")
      (node (ref "H1") (pin "7") (pinfunction "7_7") (pintype "unspecified"))
    )
    (net (code "48") (name "Net-(D1-K)") (class "Default")
      (node (ref "D1") (pin "1") (pinfunction "K_1") (pintype "unspecified"))
      (node (ref "Q2") (pin "3") (pinfunction "C_3") (pintype "input"))
      (node (ref "R10") (pin "1") (pinfunction "1_1") (pintype "unspecified"))
    )
    (net (code "49") (name "Net-(D2-A)") (class "Default")
      (node (ref "D2") (pin "2") (pinfunction "A_2") (pintype "unspecified"))
      (node (ref "DC2") (pin "1") (pinfunction "1_1") (pintype "unspecified"))
    )
    (net (code "50") (name "Net-(D3-A)") (class "Default")
      (node (ref "D3") (pin "2") (pinfunction "A_2") (pintype "unspecified"))
      (node (ref "R5") (pin "2") (pinfunction "2_2") (pintype "input"))
    )
    (net (code "51") (name "Net-(J1-Pad3)") (class "Default")
      (node (ref "J1") (pin "3") (pinfunction "3_3") (pintype "input"))
      (node (ref "R13") (pin "1") (pinfunction "1_1") (pintype "unspecified"))
    )
    (net (code "52") (name "Net-(J1-Pad4)") (class "Default")
      (node (ref "J1") (pin "4") (pinfunction "4_4") (pintype "input"))
      (node (ref "R14") (pin "2") (pinfunction "2_2") (pintype "unspecified"))
    )
    (net (code "53") (name "Net-(LED1-A)") (class "Default")
      (node (ref "LED1") (pin "2") (pinfunction "A_2") (pintype "input"))
      (node (ref "R7") (pin "2") (pinfunction "2_2") (pintype "input"))
    )
    (net (code "54") (name "Net-(LED2-A)") (class "Default")
      (node (ref "LED2") (pin "2") (pinfunction "A_2") (pintype "input"))
      (node (ref "R8") (pin "2") (pinfunction "2_2") (pintype "input"))
    )
    (net (code "55") (name "Net-(Q2-B)") (class "Default")
      (node (ref "Q2") (pin "1") (pinfunction "B_1") (pintype "input"))
      (node (ref "R9") (pin "1") (pinfunction "1_1") (pintype "input"))
    )
    (net (code "56") (name "Net-(Q2-E)") (class "Default")
      (node (ref "Q2") (pin "2") (pinfunction "E_2") (pintype "input"))
      (node (ref "R11") (pin "2") (pinfunction "2_2") (pintype "input"))
      (node (ref "U4") (pin "14") (pinfunction "RTS#_14") (pintype "unspecified"))
    )
    (net (code "57") (name "Net-(Q3-B)") (class "Default")
      (node (ref "Q3") (pin "1") (pinfunction "B_1") (pintype "input"))
      (node (ref "R11") (pin "1") (pinfunction "1_1") (pintype "input"))
    )
    (net (code "58") (name "Net-(Q3-C)") (class "Default")
      (node (ref "Q3") (pin "3") (pinfunction "C_3") (pintype "input"))
      (node (ref "R12") (pin "2") (pinfunction "2_2") (pintype "input"))
    )
    (net (code "59") (name "Net-(Q4-B)") (class "Default")
      (node (ref "Q4") (pin "1") (pinfunction "B_1") (pintype "input"))
      (node (ref "R16") (pin "1") (pinfunction "1_1") (pintype "input"))
      (node (ref "R17") (pin "2") (pinfunction "2_2") (pintype "unspecified"))
    )
    (net (code "60") (name "Net-(Q4-C)") (class "Default")
      (node (ref "Q4") (pin "3") (pinfunction "C_3") (pintype "input"))
      (node (ref "U2") (pin "2") (pinfunction "-_2") (pintype "unspecified"))
    )
    (net (code "61") (name "Net-(U1-PC14{slash}OSC32_IN)") (class "Default")
      (node (ref "C1") (pin "1") (pinfunction "1_1") (pintype "unspecified"))
      (node (ref "U1") (pin "3") (pinfunction "PC14/OSC32_IN_3") (pintype "unspecified"))
      (node (ref "X1") (pin "2") (pinfunction "2_2") (pintype "unspecified"))
    )
    (net (code "62") (name "Net-(U1-PC15-OSC32_OUT)") (class "Default")
      (node (ref "C19") (pin "1") (pinfunction "1_1") (pintype "unspecified"))
      (node (ref "U1") (pin "4") (pinfunction "PC15-OSC32_OUT_4") (pintype "unspecified"))
      (node (ref "X1") (pin "1") (pinfunction "1_1") (pintype "unspecified"))
    )
    (net (code "63") (name "Net-(U1-PD0-OSC_IN)") (class "Default")
      (node (ref "C2") (pin "2") (pinfunction "2_2") (pintype "unspecified"))
      (node (ref "U1") (pin "5") (pinfunction "PD0-OSC_IN_5") (pintype "unspecified"))
      (node (ref "X2") (pin "1") (pinfunction "OSC1_1") (pintype "input"))
    )
    (net (code "64") (name "Net-(U1-PD1-OSC_OUT)") (class "Default")
      (node (ref "C3") (pin "2") (pinfunction "2_2") (pintype "unspecified"))
      (node (ref "U1") (pin "6") (pinfunction "PD1-OSC_OUT_6") (pintype "unspecified"))
      (node (ref "X2") (pin "2") (pinfunction "OSC2_2") (pintype "input"))
    )
    (net (code "65") (name "Net-(U4-DTR#)") (class "Default")
      (node (ref "R9") (pin "2") (pinfunction "2_2") (pintype "input"))
      (node (ref "U4") (pin "13") (pinfunction "DTR#_13") (pintype "unspecified"))
    )
    (net (code "66") (name "Net-(U4-V3)") (class "Default")
      (node (ref "C21") (pin "2") (pinfunction "2_2") (pintype "unspecified"))
      (node (ref "U4") (pin "4") (pinfunction "V3_4") (pintype "unspecified"))
    )
    (net (code "67") (name "PA1") (class "Default")
      (node (ref "LED1") (pin "1") (pinfunction "C_1") (pintype "input"))
      (node (ref "U1") (pin "15") (pinfunction "PA1_15") (pintype "unspecified"))
    )
    (net (code "68") (name "RESET") (class "Default")
      (node (ref "C10") (pin "2") (pinfunction "2_2") (pintype "unspecified"))
      (node (ref "C11") (pin "2") (pinfunction "2_2") (pintype "unspecified"))
      (node (ref "C12") (pin "2") (pinfunction "2_2") (pintype "unspecified"))
      (node (ref "C13") (pin "2") (pinfunction "2_2") (pintype "unspecified"))
      (node (ref "D1") (pin "2") (pinfunction "A_2") (pintype "unspecified"))
      (node (ref "KEY1") (pin "1") (pinfunction "1_1") (pintype "unspecified"))
      (node (ref "KEY2") (pin "1") (pinfunction "1_1") (pintype "unspecified"))
      (node (ref "KEY3") (pin "1") (pinfunction "1_1") (pintype "unspecified"))
      (node (ref "KEY4") (pin "1") (pinfunction "1_1") (pintype "unspecified"))
      (node (ref "R1") (pin "1") (pinfunction "1_1") (pintype "unspecified"))
      (node (ref "R2") (pin "1") (pinfunction "1_1") (pintype "unspecified"))
      (node (ref "R3") (pin "1") (pinfunction "1_1") (pintype "unspecified"))
      (node (ref "R4") (pin "1") (pinfunction "1_1") (pintype "unspecified"))
      (node (ref "U1") (pin "7") (pinfunction "NRST_7") (pintype "unspecified"))
    )
    (net (code "69") (name "RXD") (class "Default")
      (node (ref "U1") (pin "43") (pinfunction "PA10_43") (pintype "unspecified"))
      (node (ref "U4") (pin "3") (pinfunction "RXD_3") (pintype "unspecified"))
    )
    (net (code "70") (name "SWCLK") (class "Default")
      (node (ref "H2") (pin "3") (pinfunction "3_3") (pintype "unspecified"))
      (node (ref "U1") (pin "49") (pinfunction "PA14_49") (pintype "unspecified"))
    )
    (net (code "71") (name "SWDIO") (class "Default")
      (node (ref "H2") (pin "2") (pinfunction "2_2") (pintype "unspecified"))
      (node (ref "U1") (pin "46") (pinfunction "PA13_46") (pintype "unspecified"))
    )
    (net (code "72") (name "TXD") (class "Default")
      (node (ref "U1") (pin "42") (pinfunction "PA9_42") (pintype "unspecified"))
      (node (ref "U4") (pin "2") (pinfunction "TXD_2") (pintype "unspecified"))
    )
    (net (code "73") (name "T_CS") (class "Default")
      (node (ref "H1") (pin "35") (pinfunction "35_35") (pintype "unspecified"))
      (node (ref "U1") (pin "2") (pinfunction "PC13/TAMPERRTC/RTC_2") (pintype "unspecified"))
    )
    (net (code "74") (name "T_MISO") (class "Default")
      (node (ref "H1") (pin "31") (pinfunction "31_31") (pintype "unspecified"))
      (node (ref "U1") (pin "10") (pinfunction "PC2_10") (pintype "unspecified"))
    )
    (net (code "75") (name "T_MOSI") (class "Default")
      (node (ref "H1") (pin "32") (pinfunction "32_32") (pintype "unspecified"))
      (node (ref "U1") (pin "11") (pinfunction "PC3_11") (pintype "unspecified"))
    )
    (net (code "76") (name "T_PEN") (class "Default")
      (node (ref "H1") (pin "33") (pinfunction "33_33") (pintype "unspecified"))
      (node (ref "U1") (pin "9") (pinfunction "PC1_9") (pintype "unspecified"))
    )
    (net (code "77") (name "T_SCK") (class "Default")
      (node (ref "H1") (pin "36") (pinfunction "36_36") (pintype "unspecified"))
      (node (ref "U1") (pin "8") (pinfunction "PC0_8") (pintype "unspecified"))
    )
    (net (code "78") (name "VBAT") (class "Default")
      (node (ref "D3") (pin "1") (pinfunction "K_1") (pintype "unspecified"))
      (node (ref "U1") (pin "1") (pinfunction "VBAT_1") (pintype "unspecified"))
    )
    (net (code "79") (name "VCC") (class "Default")
      (node (ref "C14") (pin "1") (pinfunction "1_1") (pintype "unspecified"))
      (node (ref "C20") (pin "1") (pinfunction "1_1") (pintype "unspecified"))
      (node (ref "C4") (pin "2") (pinfunction "2_2") (pintype "unspecified"))
      (node (ref "C5") (pin "2") (pinfunction "2_2") (pintype "unspecified"))
      (node (ref "C6") (pin "2") (pinfunction "2_2") (pintype "unspecified"))
      (node (ref "C7") (pin "2") (pinfunction "2_2") (pintype "unspecified"))
      (node (ref "C8") (pin "2") (pinfunction "2_2") (pintype "unspecified"))
      (node (ref "C9") (pin "2") (pinfunction "2_2") (pintype "unspecified"))
      (node (ref "J2") (pin "1") (pinfunction "1_1") (pintype "unspecified"))
      (node (ref "R1") (pin "2") (pinfunction "2_2") (pintype "unspecified"))
      (node (ref "R2") (pin "2") (pinfunction "2_2") (pintype "unspecified"))
      (node (ref "R3") (pin "2") (pinfunction "2_2") (pintype "unspecified"))
      (node (ref "R4") (pin "2") (pinfunction "2_2") (pintype "unspecified"))
      (node (ref "R6") (pin "2") (pinfunction "2_2") (pintype "input"))
      (node (ref "U1") (pin "13") (pinfunction "VDDA_13") (pintype "unspecified"))
      (node (ref "U1") (pin "19") (pinfunction "VDD_4_19") (pintype "unspecified"))
      (node (ref "U1") (pin "32") (pinfunction "VDD_1_32") (pintype "unspecified"))
      (node (ref "U1") (pin "48") (pinfunction "VDD_2_48") (pintype "unspecified"))
      (node (ref "U2") (pin "1") (pinfunction "+_1") (pintype "unspecified"))
      (node (ref "U4") (pin "16") (pinfunction "VCC_16") (pintype "unspecified"))
    )
    (net (code "80") (name "VIN") (class "Default")
      (node (ref "C17") (pin "2") (pinfunction "2_2") (pintype "unspecified"))
      (node (ref "D2") (pin "1") (pinfunction "C_1") (pintype "unspecified"))
      (node (ref "J2") (pin "6") (pinfunction "6_6") (pintype "unspecified"))
      (node (ref "LDO1") (pin "1") (pinfunction "IN_1") (pintype "unspecified"))
    )
    (net (code "81") (name "unconnected-(DC2-Pad3)") (class "Default")
      (node (ref "DC2") (pin "3") (pinfunction "3_3") (pintype "unspecified"))
    )
    (net (code "82") (name "unconnected-(H1-Pad34)") (class "Default")
      (node (ref "H1") (pin "34") (pinfunction "34_34") (pintype "unspecified"))
    )
    (net (code "83") (name "unconnected-(Q1-B-Pad1)") (class "Default")
      (node (ref "Q1") (pin "1") (pinfunction "B_1") (pintype "input"))
    )
    (net (code "84") (name "unconnected-(Q1-C-Pad3)") (class "Default")
      (node (ref "Q1") (pin "3") (pinfunction "C_3") (pintype "input"))
    )
    (net (code "85") (name "unconnected-(Q1-E-Pad2)") (class "Default")
      (node (ref "Q1") (pin "2") (pinfunction "E_2") (pintype "input"))
    )
    (net (code "86") (name "unconnected-(U1-VDD_3-Pad64)") (class "Default")
      (node (ref "U1") (pin "64") (pinfunction "VDD_3_64") (pintype "unspecified"))
    )
    (net (code "87") (name "unconnected-(U1-VSS_3-Pad63)") (class "Default")
      (node (ref "U1") (pin "63") (pinfunction "VSS_3_63") (pintype "unspecified"))
    )
    (net (code "88") (name "unconnected-(U4-CTS#-Pad9)") (class "Default")
      (node (ref "U4") (pin "9") (pinfunction "CTS#_9") (pintype "unspecified"))
    )
    (net (code "89") (name "unconnected-(U4-DCD#-Pad12)") (class "Default")
      (node (ref "U4") (pin "12") (pinfunction "DCD#_12") (pintype "unspecified"))
    )
    (net (code "90") (name "unconnected-(U4-DSR#-Pad10)") (class "Default")
      (node (ref "U4") (pin "10") (pinfunction "DSR#_10") (pintype "unspecified"))
    )
    (net (code "91") (name "unconnected-(U4-NC.-Pad7)") (class "Default")
      (node (ref "U4") (pin "7") (pinfunction "NC._7") (pintype "unspecified"))
    )
    (net (code "92") (name "unconnected-(U4-OUT#-Pad8)") (class "Default")
      (node (ref "U4") (pin "8") (pinfunction "OUT#_8") (pintype "unspecified"))
    )
    (net (code "93") (name "unconnected-(U4-R232-Pad15)") (class "Default")
      (node (ref "U4") (pin "15") (pinfunction "R232_15") (pintype "unspecified"))
    )
    (net (code "94") (name "unconnected-(U4-RI#-Pad11)") (class "Default")
      (node (ref "U4") (pin "11") (pinfunction "RI#_11") (pintype "unspecified"))
    )
    (net (code "95") (name "unconnected-(USB1-CC1-Pad4)") (class "Default")
      (node (ref "USB1") (pin "4") (pinfunction "CC1_4") (pintype "unspecified"))
    )
    (net (code "96") (name "unconnected-(USB1-CC2-Pad10)") (class "Default")
      (node (ref "USB1") (pin "10") (pinfunction "CC2_10") (pintype "unspecified"))
    )
    (net (code "97") (name "unconnected-(USB1-SBU1-Pad9)") (class "Default")
      (node (ref "USB1") (pin "9") (pinfunction "SBU1_9") (pintype "unspecified"))
    )
    (net (code "98") (name "unconnected-(USB1-SBU2-Pad3)") (class "Default")
      (node (ref "USB1") (pin "3") (pinfunction "SBU2_3") (pintype "unspecified"))
    )
  )
)
